# RelayController.net
KiCad netlist of a schematic drawn in Altium Designer
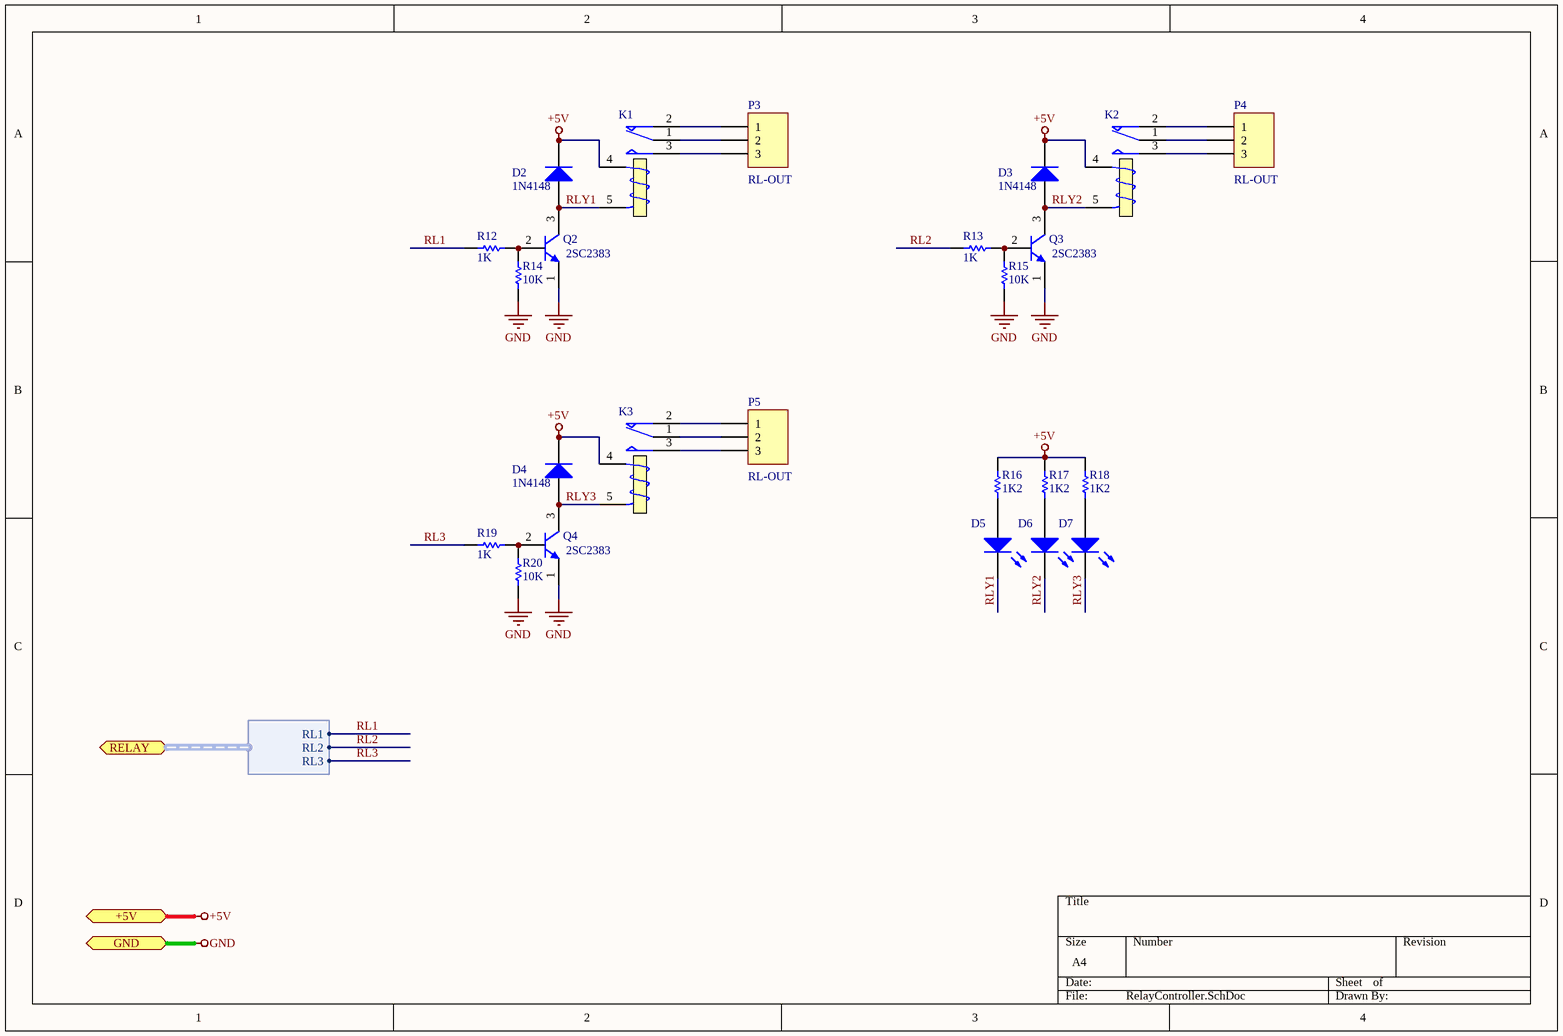
[diagram p0: RelayController.SchDoc]

(export (version "E")
  (design (tool "Eeschema 10.0.6"))
  (components
    (comp (ref "D2")
      (value "1N4148")
      (footprint "D-DO213-AA")
      (description "High Conductance Fast Diode")
      (libsource (lib "Miscellaneous Devices") (part "Diode 1N4148"))
    )
    (comp (ref "D3")
      (value "1N4148")
      (footprint "D-DO213-AA")
      (description "High Conductance Fast Diode")
      (libsource (lib "Miscellaneous Devices") (part "Diode 1N4148"))
    )
    (comp (ref "D4")
      (value "1N4148")
      (footprint "D-DO213-AA")
      (description "High Conductance Fast Diode")
      (libsource (lib "Miscellaneous Devices") (part "Diode 1N4148"))
    )
    (comp (ref "D5")
      (value "SMD0805-RED")
      (footprint "LED-0805")
      (description "Typical INFRARED GaAs LED")
      (libsource (lib "Miscellaneous Devices") (part "LED0"))
    )
    (comp (ref "D6")
      (value "SMD0805-RED")
      (footprint "LED-0805")
      (description "Typical INFRARED GaAs LED")
      (libsource (lib "Miscellaneous Devices") (part "LED0"))
    )
    (comp (ref "D7")
      (value "SMD0805-RED")
      (footprint "LED-0805")
      (description "Typical INFRARED GaAs LED")
      (libsource (lib "Miscellaneous Devices") (part "LED0"))
    )
    (comp (ref "K1")
      (value "RL-5P-10A")
      (footprint "RL-5P-10A")
      (description "SPDT Relay")
      (libsource (lib "Miscellaneous Devices") (part "Relay"))
    )
    (comp (ref "K2")
      (value "RL-5P-10A")
      (footprint "RL-5P-10A")
      (description "SPDT Relay")
      (libsource (lib "Miscellaneous Devices") (part "Relay"))
    )
    (comp (ref "K3")
      (value "RL-5P-10A")
      (footprint "RL-5P-10A")
      (description "SPDT Relay")
      (libsource (lib "Miscellaneous Devices") (part "Relay"))
    )
    (comp (ref "P3")
      (value "RL-OUT")
      (footprint "TER-KF128-3P")
      (description "Header, 3-Pin")
      (fields (field (name "Comment") "KF128-3P"))
      (libsource (lib "Miscellaneous Connectors") (part "Header 3"))
    )
    (comp (ref "P4")
      (value "RL-OUT")
      (footprint "TER-KF128-3P")
      (description "Header, 3-Pin")
      (fields (field (name "Comment") "KF128-3P"))
      (libsource (lib "Miscellaneous Connectors") (part "Header 3"))
    )
    (comp (ref "P5")
      (value "RL-OUT")
      (footprint "TER-KF128-3P")
      (description "Header, 3-Pin")
      (fields (field (name "Comment") "KF128-3P"))
      (libsource (lib "Miscellaneous Connectors") (part "Header 3"))
    )
    (comp (ref "Q2")
      (value "2SC2383")
      (footprint "TO-92AB")
      (description "NPN Bipolar Transistor")
      (fields (field (name "Comment") "C2383"))
      (libsource (lib "Miscellaneous Devices") (part "NPN"))
    )
    (comp (ref "Q3")
      (value "2SC2383")
      (footprint "TO-92AB")
      (description "NPN Bipolar Transistor")
      (fields (field (name "Comment") "C2383"))
      (libsource (lib "Miscellaneous Devices") (part "NPN"))
    )
    (comp (ref "Q4")
      (value "2SC2383")
      (footprint "TO-92AB")
      (description "NPN Bipolar Transistor")
      (fields (field (name "Comment") "C2383"))
      (libsource (lib "Miscellaneous Devices") (part "NPN"))
    )
    (comp (ref "R12")
      (value "1K")
      (footprint "R-0805")
      (description "Resistor")
      (fields (field (name "PUBLISHER") "Altium Limited"))
      (libsource (lib "Miscellaneous Devices") (part "Res1"))
    )
    (comp (ref "R13")
      (value "1K")
      (footprint "R-0805")
      (description "Resistor")
      (fields (field (name "PUBLISHER") "Altium Limited"))
      (libsource (lib "Miscellaneous Devices") (part "Res1"))
    )
    (comp (ref "R14")
      (value "10K")
      (footprint "R-0805")
      (description "Resistor")
      (fields (field (name "PUBLISHER") "Altium Limited"))
      (libsource (lib "Miscellaneous Devices") (part "Res1"))
    )
    (comp (ref "R15")
      (value "10K")
      (footprint "R-0805")
      (description "Resistor")
      (fields (field (name "PUBLISHER") "Altium Limited"))
      (libsource (lib "Miscellaneous Devices") (part "Res1"))
    )
    (comp (ref "R16")
      (value "1K2")
      (footprint "R-0805")
      (description "Resistor")
      (fields (field (name "PUBLISHER") "Altium Limited"))
      (libsource (lib "Miscellaneous Devices") (part "Res1"))
    )
    (comp (ref "R17")
      (value "1K2")
      (footprint "R-0805")
      (description "Resistor")
      (fields (field (name "PUBLISHER") "Altium Limited"))
      (libsource (lib "Miscellaneous Devices") (part "Res1"))
    )
    (comp (ref "R18")
      (value "1K2")
      (footprint "R-0805")
      (description "Resistor")
      (fields (field (name "PUBLISHER") "Altium Limited"))
      (libsource (lib "Miscellaneous Devices") (part "Res1"))
    )
    (comp (ref "R19")
      (value "1K")
      (footprint "R-0805")
      (description "Resistor")
      (fields (field (name "PUBLISHER") "Altium Limited"))
      (libsource (lib "Miscellaneous Devices") (part "Res1"))
    )
    (comp (ref "R20")
      (value "10K")
      (footprint "R-0805")
      (description "Resistor")
      (fields (field (name "PUBLISHER") "Altium Limited"))
      (libsource (lib "Miscellaneous Devices") (part "Res1"))
    )
  )
  (nets
    (net (code "2") (name "+5V") (class "Default")
      (node (ref "D2") (pin "2") (pinfunction "K_2") (pintype "passive"))
      (node (ref "D3") (pin "2") (pinfunction "K_2") (pintype "passive"))
      (node (ref "D4") (pin "2") (pinfunction "K_2") (pintype "passive"))
      (node (ref "K1") (pin "4") (pinfunction "T1_4") (pintype "passive"))
      (node (ref "K2") (pin "4") (pinfunction "T1_4") (pintype "passive"))
      (node (ref "K3") (pin "4") (pinfunction "T1_4") (pintype "passive"))
      (node (ref "R16") (pin "2") (pinfunction "2_2") (pintype "passive"))
      (node (ref "R17") (pin "2") (pinfunction "2_2") (pintype "passive"))
      (node (ref "R18") (pin "2") (pinfunction "2_2") (pintype "passive"))
    )
    (net (code "3") (name "/RL1") (class "Default")
      (node (ref "R12") (pin "2") (pinfunction "2_2") (pintype "passive"))
    )
    (net (code "4") (name "/RL2") (class "Default")
      (node (ref "R13") (pin "2") (pinfunction "2_2") (pintype "passive"))
    )
    (net (code "5") (name "/RL3") (class "Default")
      (node (ref "R19") (pin "2") (pinfunction "2_2") (pintype "passive"))
    )
    (net (code "6") (name "/RLY1") (class "Default")
      (node (ref "D2") (pin "1") (pinfunction "A_1") (pintype "passive"))
      (node (ref "D5") (pin "2") (pinfunction "K_2") (pintype "passive"))
      (node (ref "K1") (pin "5") (pinfunction "T2_5") (pintype "passive"))
      (node (ref "Q2") (pin "3") (pinfunction "C_3") (pintype "passive"))
    )
    (net (code "7") (name "/RLY2") (class "Default")
      (node (ref "D3") (pin "1") (pinfunction "A_1") (pintype "passive"))
      (node (ref "D6") (pin "2") (pinfunction "K_2") (pintype "passive"))
      (node (ref "K2") (pin "5") (pinfunction "T2_5") (pintype "passive"))
      (node (ref "Q3") (pin "3") (pinfunction "C_3") (pintype "passive"))
    )
    (net (code "8") (name "/RLY3") (class "Default")
      (node (ref "D4") (pin "1") (pinfunction "A_1") (pintype "passive"))
      (node (ref "D7") (pin "2") (pinfunction "K_2") (pintype "passive"))
      (node (ref "K3") (pin "5") (pinfunction "T2_5") (pintype "passive"))
      (node (ref "Q4") (pin "3") (pinfunction "C_3") (pintype "passive"))
    )
    (net (code "10") (name "GND") (class "Default")
      (node (ref "Q2") (pin "1") (pinfunction "E_1") (pintype "passive"))
      (node (ref "Q3") (pin "1") (pinfunction "E_1") (pintype "passive"))
      (node (ref "Q4") (pin "1") (pinfunction "E_1") (pintype "passive"))
      (node (ref "R14") (pin "2") (pinfunction "2_2") (pintype "passive"))
      (node (ref "R15") (pin "2") (pinfunction "2_2") (pintype "passive"))
      (node (ref "R20") (pin "2") (pinfunction "2_2") (pintype "passive"))
    )
    (net (code "11") (name "Net-(D5-A)") (class "Default")
      (node (ref "D5") (pin "1") (pinfunction "A_1") (pintype "passive"))
      (node (ref "R16") (pin "1") (pinfunction "1_1") (pintype "passive"))
    )
    (net (code "12") (name "Net-(D6-A)") (class "Default")
      (node (ref "D6") (pin "1") (pinfunction "A_1") (pintype "passive"))
      (node (ref "R17") (pin "1") (pinfunction "1_1") (pintype "passive"))
    )
    (net (code "13") (name "Net-(D7-A)") (class "Default")
      (node (ref "D7") (pin "1") (pinfunction "A_1") (pintype "passive"))
      (node (ref "R18") (pin "1") (pinfunction "1_1") (pintype "passive"))
    )
    (net (code "14") (name "Net-(K1-COM)") (class "Default")
      (node (ref "K1") (pin "1") (pinfunction "COM_1") (pintype "passive"))
      (node (ref "P3") (pin "2") (pinfunction "2_2") (pintype "passive"))
    )
    (net (code "15") (name "Net-(K1-NC)") (class "Default")
      (node (ref "K1") (pin "2") (pinfunction "NC_2") (pintype "passive"))
      (node (ref "P3") (pin "1") (pinfunction "1_1") (pintype "passive"))
    )
    (net (code "16") (name "Net-(K1-NO)") (class "Default")
      (node (ref "K1") (pin "3") (pinfunction "NO_3") (pintype "passive"))
      (node (ref "P3") (pin "3") (pinfunction "3_3") (pintype "passive"))
    )
    (net (code "17") (name "Net-(K2-COM)") (class "Default")
      (node (ref "K2") (pin "1") (pinfunction "COM_1") (pintype "passive"))
      (node (ref "P4") (pin "2") (pinfunction "2_2") (pintype "passive"))
    )
    (net (code "18") (name "Net-(K2-NC)") (class "Default")
      (node (ref "K2") (pin "2") (pinfunction "NC_2") (pintype "passive"))
      (node (ref "P4") (pin "1") (pinfunction "1_1") (pintype "passive"))
    )
    (net (code "19") (name "Net-(K2-NO)") (class "Default")
      (node (ref "K2") (pin "3") (pinfunction "NO_3") (pintype "passive"))
      (node (ref "P4") (pin "3") (pinfunction "3_3") (pintype "passive"))
    )
    (net (code "20") (name "Net-(K3-COM)") (class "Default")
      (node (ref "K3") (pin "1") (pinfunction "COM_1") (pintype "passive"))
      (node (ref "P5") (pin "2") (pinfunction "2_2") (pintype "passive"))
    )
    (net (code "21") (name "Net-(K3-NC)") (class "Default")
      (node (ref "K3") (pin "2") (pinfunction "NC_2") (pintype "passive"))
      (node (ref "P5") (pin "1") (pinfunction "1_1") (pintype "passive"))
    )
    (net (code "22") (name "Net-(K3-NO)") (class "Default")
      (node (ref "K3") (pin "3") (pinfunction "NO_3") (pintype "passive"))
      (node (ref "P5") (pin "3") (pinfunction "3_3") (pintype "passive"))
    )
    (net (code "23") (name "Net-(Q2-B)") (class "Default")
      (node (ref "Q2") (pin "2") (pinfunction "B_2") (pintype "passive"))
      (node (ref "R12") (pin "1") (pinfunction "1_1") (pintype "passive"))
      (node (ref "R14") (pin "1") (pinfunction "1_1") (pintype "passive"))
    )
    (net (code "24") (name "Net-(Q3-B)") (class "Default")
      (node (ref "Q3") (pin "2") (pinfunction "B_2") (pintype "passive"))
      (node (ref "R13") (pin "1") (pinfunction "1_1") (pintype "passive"))
      (node (ref "R15") (pin "1") (pinfunction "1_1") (pintype "passive"))
    )
    (net (code "25") (name "Net-(Q4-B)") (class "Default")
      (node (ref "Q4") (pin "2") (pinfunction "B_2") (pintype "passive"))
      (node (ref "R19") (pin "1") (pinfunction "1_1") (pintype "passive"))
      (node (ref "R20") (pin "1") (pinfunction "1_1") (pintype "passive"))
    )
  )
)
